# input_wheel.net
KiCad netlist of a schematic drawn in EAGLE
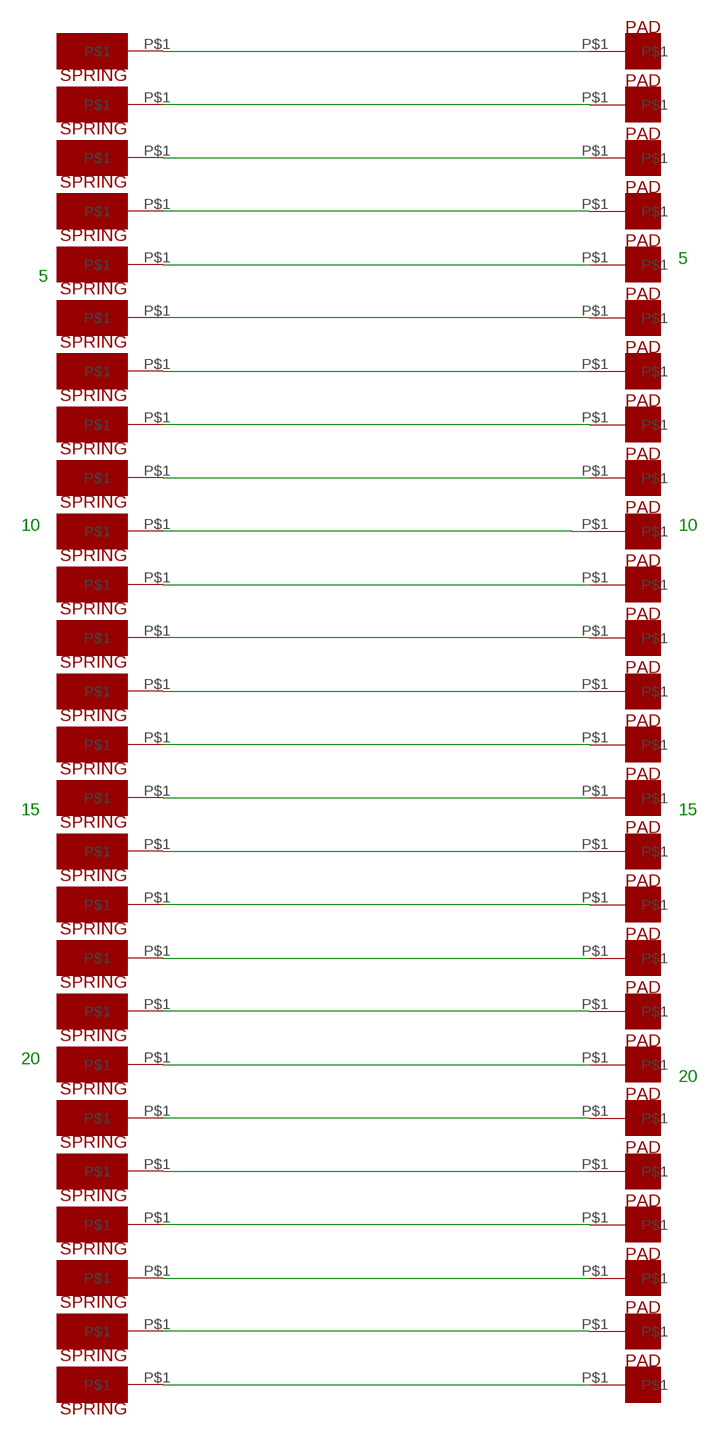
[diagram p0: schematic, sheet 1]

(export (version "E")
  (design (tool "Eeschema 10.0.6"))
  (components
    (comp (ref "U$1")
      (value "CONTACT")
      (footprint "eagle-import:CONTACT")
      (libsource (lib "eagle-import") (part "CONTACT"))
    )
    (comp (ref "U$2")
      (value "CONTACT")
      (footprint "eagle-import:CONTACT")
      (libsource (lib "eagle-import") (part "CONTACT"))
    )
    (comp (ref "U$3")
      (value "CONTACT")
      (footprint "eagle-import:CONTACT")
      (libsource (lib "eagle-import") (part "CONTACT"))
    )
    (comp (ref "U$4")
      (value "CONTACT")
      (footprint "eagle-import:CONTACT")
      (libsource (lib "eagle-import") (part "CONTACT"))
    )
    (comp (ref "U$5")
      (value "CONTACT")
      (footprint "eagle-import:CONTACT")
      (libsource (lib "eagle-import") (part "CONTACT"))
    )
    (comp (ref "U$6")
      (value "CONTACT")
      (footprint "eagle-import:CONTACT")
      (libsource (lib "eagle-import") (part "CONTACT"))
    )
    (comp (ref "U$7")
      (value "CONTACT")
      (footprint "eagle-import:CONTACT")
      (libsource (lib "eagle-import") (part "CONTACT"))
    )
    (comp (ref "U$8")
      (value "CONTACT")
      (footprint "eagle-import:CONTACT")
      (libsource (lib "eagle-import") (part "CONTACT"))
    )
    (comp (ref "U$9")
      (value "CONTACT")
      (footprint "eagle-import:CONTACT")
      (libsource (lib "eagle-import") (part "CONTACT"))
    )
    (comp (ref "U$10")
      (value "CONTACT")
      (footprint "eagle-import:CONTACT")
      (libsource (lib "eagle-import") (part "CONTACT"))
    )
    (comp (ref "U$11")
      (value "CONTACT")
      (footprint "eagle-import:CONTACT")
      (libsource (lib "eagle-import") (part "CONTACT"))
    )
    (comp (ref "U$12")
      (value "CONTACT")
      (footprint "eagle-import:CONTACT")
      (libsource (lib "eagle-import") (part "CONTACT"))
    )
    (comp (ref "U$13")
      (value "CONTACT")
      (footprint "eagle-import:CONTACT")
      (libsource (lib "eagle-import") (part "CONTACT"))
    )
    (comp (ref "U$14")
      (value "CONTACT")
      (footprint "eagle-import:CONTACT")
      (libsource (lib "eagle-import") (part "CONTACT"))
    )
    (comp (ref "U$15")
      (value "CONTACT")
      (footprint "eagle-import:CONTACT")
      (libsource (lib "eagle-import") (part "CONTACT"))
    )
    (comp (ref "U$16")
      (value "CONTACT")
      (footprint "eagle-import:CONTACT")
      (libsource (lib "eagle-import") (part "CONTACT"))
    )
    (comp (ref "U$17")
      (value "CONTACT")
      (footprint "eagle-import:CONTACT")
      (libsource (lib "eagle-import") (part "CONTACT"))
    )
    (comp (ref "U$18")
      (value "CONTACT")
      (footprint "eagle-import:CONTACT")
      (libsource (lib "eagle-import") (part "CONTACT"))
    )
    (comp (ref "U$19")
      (value "CONTACT")
      (footprint "eagle-import:CONTACT")
      (libsource (lib "eagle-import") (part "CONTACT"))
    )
    (comp (ref "U$20")
      (value "CONTACT")
      (footprint "eagle-import:CONTACT")
      (libsource (lib "eagle-import") (part "CONTACT"))
    )
    (comp (ref "U$21")
      (value "CONTACT")
      (footprint "eagle-import:CONTACT")
      (libsource (lib "eagle-import") (part "CONTACT"))
    )
    (comp (ref "U$22")
      (value "CONTACT")
      (footprint "eagle-import:CONTACT")
      (libsource (lib "eagle-import") (part "CONTACT"))
    )
    (comp (ref "U$23")
      (value "CONTACT")
      (footprint "eagle-import:CONTACT")
      (libsource (lib "eagle-import") (part "CONTACT"))
    )
    (comp (ref "U$24")
      (value "CONTACT")
      (footprint "eagle-import:CONTACT")
      (libsource (lib "eagle-import") (part "CONTACT"))
    )
    (comp (ref "U$25")
      (value "CONTACT")
      (footprint "eagle-import:CONTACT")
      (libsource (lib "eagle-import") (part "CONTACT"))
    )
    (comp (ref "U$26")
      (value "CONTACT")
      (footprint "eagle-import:CONTACT")
      (libsource (lib "eagle-import") (part "CONTACT"))
    )
    (comp (ref "U$27")
      (value "SPRING")
      (footprint "eagle-import:SPRING")
      (libsource (lib "eagle-import") (part "SPRING"))
    )
    (comp (ref "U$28")
      (value "SPRING")
      (footprint "eagle-import:SPRING")
      (libsource (lib "eagle-import") (part "SPRING"))
    )
    (comp (ref "U$29")
      (value "SPRING")
      (footprint "eagle-import:SPRING")
      (libsource (lib "eagle-import") (part "SPRING"))
    )
    (comp (ref "U$30")
      (value "SPRING")
      (footprint "eagle-import:SPRING")
      (libsource (lib "eagle-import") (part "SPRING"))
    )
    (comp (ref "U$31")
      (value "SPRING")
      (footprint "eagle-import:SPRING")
      (libsource (lib "eagle-import") (part "SPRING"))
    )
    (comp (ref "U$32")
      (value "SPRING")
      (footprint "eagle-import:SPRING")
      (libsource (lib "eagle-import") (part "SPRING"))
    )
    (comp (ref "U$33")
      (value "SPRING")
      (footprint "eagle-import:SPRING")
      (libsource (lib "eagle-import") (part "SPRING"))
    )
    (comp (ref "U$34")
      (value "SPRING")
      (footprint "eagle-import:SPRING")
      (libsource (lib "eagle-import") (part "SPRING"))
    )
    (comp (ref "U$35")
      (value "SPRING")
      (footprint "eagle-import:SPRING")
      (libsource (lib "eagle-import") (part "SPRING"))
    )
    (comp (ref "U$36")
      (value "SPRING")
      (footprint "eagle-import:SPRING")
      (libsource (lib "eagle-import") (part "SPRING"))
    )
    (comp (ref "U$37")
      (value "SPRING")
      (footprint "eagle-import:SPRING")
      (libsource (lib "eagle-import") (part "SPRING"))
    )
    (comp (ref "U$38")
      (value "SPRING")
      (footprint "eagle-import:SPRING")
      (libsource (lib "eagle-import") (part "SPRING"))
    )
    (comp (ref "U$39")
      (value "SPRING")
      (footprint "eagle-import:SPRING")
      (libsource (lib "eagle-import") (part "SPRING"))
    )
    (comp (ref "U$40")
      (value "SPRING")
      (footprint "eagle-import:SPRING")
      (libsource (lib "eagle-import") (part "SPRING"))
    )
    (comp (ref "U$41")
      (value "SPRING")
      (footprint "eagle-import:SPRING")
      (libsource (lib "eagle-import") (part "SPRING"))
    )
    (comp (ref "U$42")
      (value "SPRING")
      (footprint "eagle-import:SPRING")
      (libsource (lib "eagle-import") (part "SPRING"))
    )
    (comp (ref "U$43")
      (value "SPRING")
      (footprint "eagle-import:SPRING")
      (libsource (lib "eagle-import") (part "SPRING"))
    )
    (comp (ref "U$44")
      (value "SPRING")
      (footprint "eagle-import:SPRING")
      (libsource (lib "eagle-import") (part "SPRING"))
    )
    (comp (ref "U$45")
      (value "SPRING")
      (footprint "eagle-import:SPRING")
      (libsource (lib "eagle-import") (part "SPRING"))
    )
    (comp (ref "U$46")
      (value "SPRING")
      (footprint "eagle-import:SPRING")
      (libsource (lib "eagle-import") (part "SPRING"))
    )
    (comp (ref "U$47")
      (value "SPRING")
      (footprint "eagle-import:SPRING")
      (libsource (lib "eagle-import") (part "SPRING"))
    )
    (comp (ref "U$48")
      (value "SPRING")
      (footprint "eagle-import:SPRING")
      (libsource (lib "eagle-import") (part "SPRING"))
    )
    (comp (ref "U$49")
      (value "SPRING")
      (footprint "eagle-import:SPRING")
      (libsource (lib "eagle-import") (part "SPRING"))
    )
    (comp (ref "U$50")
      (value "SPRING")
      (footprint "eagle-import:SPRING")
      (libsource (lib "eagle-import") (part "SPRING"))
    )
    (comp (ref "U$51")
      (value "SPRING")
      (footprint "eagle-import:SPRING")
      (libsource (lib "eagle-import") (part "SPRING"))
    )
    (comp (ref "U$52")
      (value "SPRING")
      (footprint "eagle-import:SPRING")
      (libsource (lib "eagle-import") (part "SPRING"))
    )
  )
  (nets
    (net (code "1") (name "Net-(U$1-PadP$1)") (class "Default")
      (node (ref "U$1") (pin "P$1") (pinfunction "P$1_P$1") (pintype "bidirectional"))
      (node (ref "U$27") (pin "P$1") (pinfunction "P$1_P$1") (pintype "bidirectional"))
    )
    (net (code "2") (name "Net-(U$2-PadP$1)") (class "Default")
      (node (ref "U$2") (pin "P$1") (pinfunction "P$1_P$1") (pintype "bidirectional"))
      (node (ref "U$28") (pin "P$1") (pinfunction "P$1_P$1") (pintype "bidirectional"))
    )
    (net (code "3") (name "Net-(U$10-PadP$1)") (class "Default")
      (node (ref "U$10") (pin "P$1") (pinfunction "P$1_P$1") (pintype "bidirectional"))
      (node (ref "U$36") (pin "P$1") (pinfunction "P$1_P$1") (pintype "bidirectional"))
    )
    (net (code "4") (name "Net-(U$11-PadP$1)") (class "Default")
      (node (ref "U$11") (pin "P$1") (pinfunction "P$1_P$1") (pintype "bidirectional"))
      (node (ref "U$37") (pin "P$1") (pinfunction "P$1_P$1") (pintype "bidirectional"))
    )
    (net (code "5") (name "Net-(U$12-PadP$1)") (class "Default")
      (node (ref "U$12") (pin "P$1") (pinfunction "P$1_P$1") (pintype "bidirectional"))
      (node (ref "U$38") (pin "P$1") (pinfunction "P$1_P$1") (pintype "bidirectional"))
    )
    (net (code "6") (name "Net-(U$13-PadP$1)") (class "Default")
      (node (ref "U$13") (pin "P$1") (pinfunction "P$1_P$1") (pintype "bidirectional"))
      (node (ref "U$39") (pin "P$1") (pinfunction "P$1_P$1") (pintype "bidirectional"))
    )
    (net (code "7") (name "Net-(U$14-PadP$1)") (class "Default")
      (node (ref "U$14") (pin "P$1") (pinfunction "P$1_P$1") (pintype "bidirectional"))
      (node (ref "U$40") (pin "P$1") (pinfunction "P$1_P$1") (pintype "bidirectional"))
    )
    (net (code "8") (name "Net-(U$15-PadP$1)") (class "Default")
      (node (ref "U$15") (pin "P$1") (pinfunction "P$1_P$1") (pintype "bidirectional"))
      (node (ref "U$41") (pin "P$1") (pinfunction "P$1_P$1") (pintype "bidirectional"))
    )
    (net (code "9") (name "Net-(U$16-PadP$1)") (class "Default")
      (node (ref "U$16") (pin "P$1") (pinfunction "P$1_P$1") (pintype "bidirectional"))
      (node (ref "U$42") (pin "P$1") (pinfunction "P$1_P$1") (pintype "bidirectional"))
    )
    (net (code "10") (name "Net-(U$17-PadP$1)") (class "Default")
      (node (ref "U$17") (pin "P$1") (pinfunction "P$1_P$1") (pintype "bidirectional"))
      (node (ref "U$43") (pin "P$1") (pinfunction "P$1_P$1") (pintype "bidirectional"))
    )
    (net (code "11") (name "Net-(U$18-PadP$1)") (class "Default")
      (node (ref "U$18") (pin "P$1") (pinfunction "P$1_P$1") (pintype "bidirectional"))
      (node (ref "U$44") (pin "P$1") (pinfunction "P$1_P$1") (pintype "bidirectional"))
    )
    (net (code "12") (name "Net-(U$19-PadP$1)") (class "Default")
      (node (ref "U$19") (pin "P$1") (pinfunction "P$1_P$1") (pintype "bidirectional"))
      (node (ref "U$45") (pin "P$1") (pinfunction "P$1_P$1") (pintype "bidirectional"))
    )
    (net (code "13") (name "Net-(U$20-PadP$1)") (class "Default")
      (node (ref "U$20") (pin "P$1") (pinfunction "P$1_P$1") (pintype "bidirectional"))
      (node (ref "U$46") (pin "P$1") (pinfunction "P$1_P$1") (pintype "bidirectional"))
    )
    (net (code "14") (name "Net-(U$21-PadP$1)") (class "Default")
      (node (ref "U$21") (pin "P$1") (pinfunction "P$1_P$1") (pintype "bidirectional"))
      (node (ref "U$47") (pin "P$1") (pinfunction "P$1_P$1") (pintype "bidirectional"))
    )
    (net (code "15") (name "Net-(U$22-PadP$1)") (class "Default")
      (node (ref "U$22") (pin "P$1") (pinfunction "P$1_P$1") (pintype "bidirectional"))
      (node (ref "U$48") (pin "P$1") (pinfunction "P$1_P$1") (pintype "bidirectional"))
    )
    (net (code "16") (name "Net-(U$23-PadP$1)") (class "Default")
      (node (ref "U$23") (pin "P$1") (pinfunction "P$1_P$1") (pintype "bidirectional"))
      (node (ref "U$49") (pin "P$1") (pinfunction "P$1_P$1") (pintype "bidirectional"))
    )
    (net (code "17") (name "Net-(U$24-PadP$1)") (class "Default")
      (node (ref "U$24") (pin "P$1") (pinfunction "P$1_P$1") (pintype "bidirectional"))
      (node (ref "U$50") (pin "P$1") (pinfunction "P$1_P$1") (pintype "bidirectional"))
    )
    (net (code "18") (name "Net-(U$25-PadP$1)") (class "Default")
      (node (ref "U$25") (pin "P$1") (pinfunction "P$1_P$1") (pintype "bidirectional"))
      (node (ref "U$51") (pin "P$1") (pinfunction "P$1_P$1") (pintype "bidirectional"))
    )
    (net (code "19") (name "Net-(U$26-PadP$1)") (class "Default")
      (node (ref "U$26") (pin "P$1") (pinfunction "P$1_P$1") (pintype "bidirectional"))
      (node (ref "U$52") (pin "P$1") (pinfunction "P$1_P$1") (pintype "bidirectional"))
    )
    (net (code "20") (name "Net-(U$29-PadP$1)") (class "Default")
      (node (ref "U$29") (pin "P$1") (pinfunction "P$1_P$1") (pintype "bidirectional"))
      (node (ref "U$3") (pin "P$1") (pinfunction "P$1_P$1") (pintype "bidirectional"))
    )
    (net (code "21") (name "Net-(U$30-PadP$1)") (class "Default")
      (node (ref "U$30") (pin "P$1") (pinfunction "P$1_P$1") (pintype "bidirectional"))
      (node (ref "U$4") (pin "P$1") (pinfunction "P$1_P$1") (pintype "bidirectional"))
    )
    (net (code "22") (name "Net-(U$31-PadP$1)") (class "Default")
      (node (ref "U$31") (pin "P$1") (pinfunction "P$1_P$1") (pintype "bidirectional"))
      (node (ref "U$5") (pin "P$1") (pinfunction "P$1_P$1") (pintype "bidirectional"))
    )
    (net (code "23") (name "Net-(U$32-PadP$1)") (class "Default")
      (node (ref "U$32") (pin "P$1") (pinfunction "P$1_P$1") (pintype "bidirectional"))
      (node (ref "U$6") (pin "P$1") (pinfunction "P$1_P$1") (pintype "bidirectional"))
    )
    (net (code "24") (name "Net-(U$33-PadP$1)") (class "Default")
      (node (ref "U$33") (pin "P$1") (pinfunction "P$1_P$1") (pintype "bidirectional"))
      (node (ref "U$7") (pin "P$1") (pinfunction "P$1_P$1") (pintype "bidirectional"))
    )
    (net (code "25") (name "Net-(U$34-PadP$1)") (class "Default")
      (node (ref "U$34") (pin "P$1") (pinfunction "P$1_P$1") (pintype "bidirectional"))
      (node (ref "U$8") (pin "P$1") (pinfunction "P$1_P$1") (pintype "bidirectional"))
    )
    (net (code "26") (name "Net-(U$35-PadP$1)") (class "Default")
      (node (ref "U$35") (pin "P$1") (pinfunction "P$1_P$1") (pintype "bidirectional"))
      (node (ref "U$9") (pin "P$1") (pinfunction "P$1_P$1") (pintype "bidirectional"))
    )
  )
)
